# design.net
KiCad netlist of a schematic drawn in Altium Designer
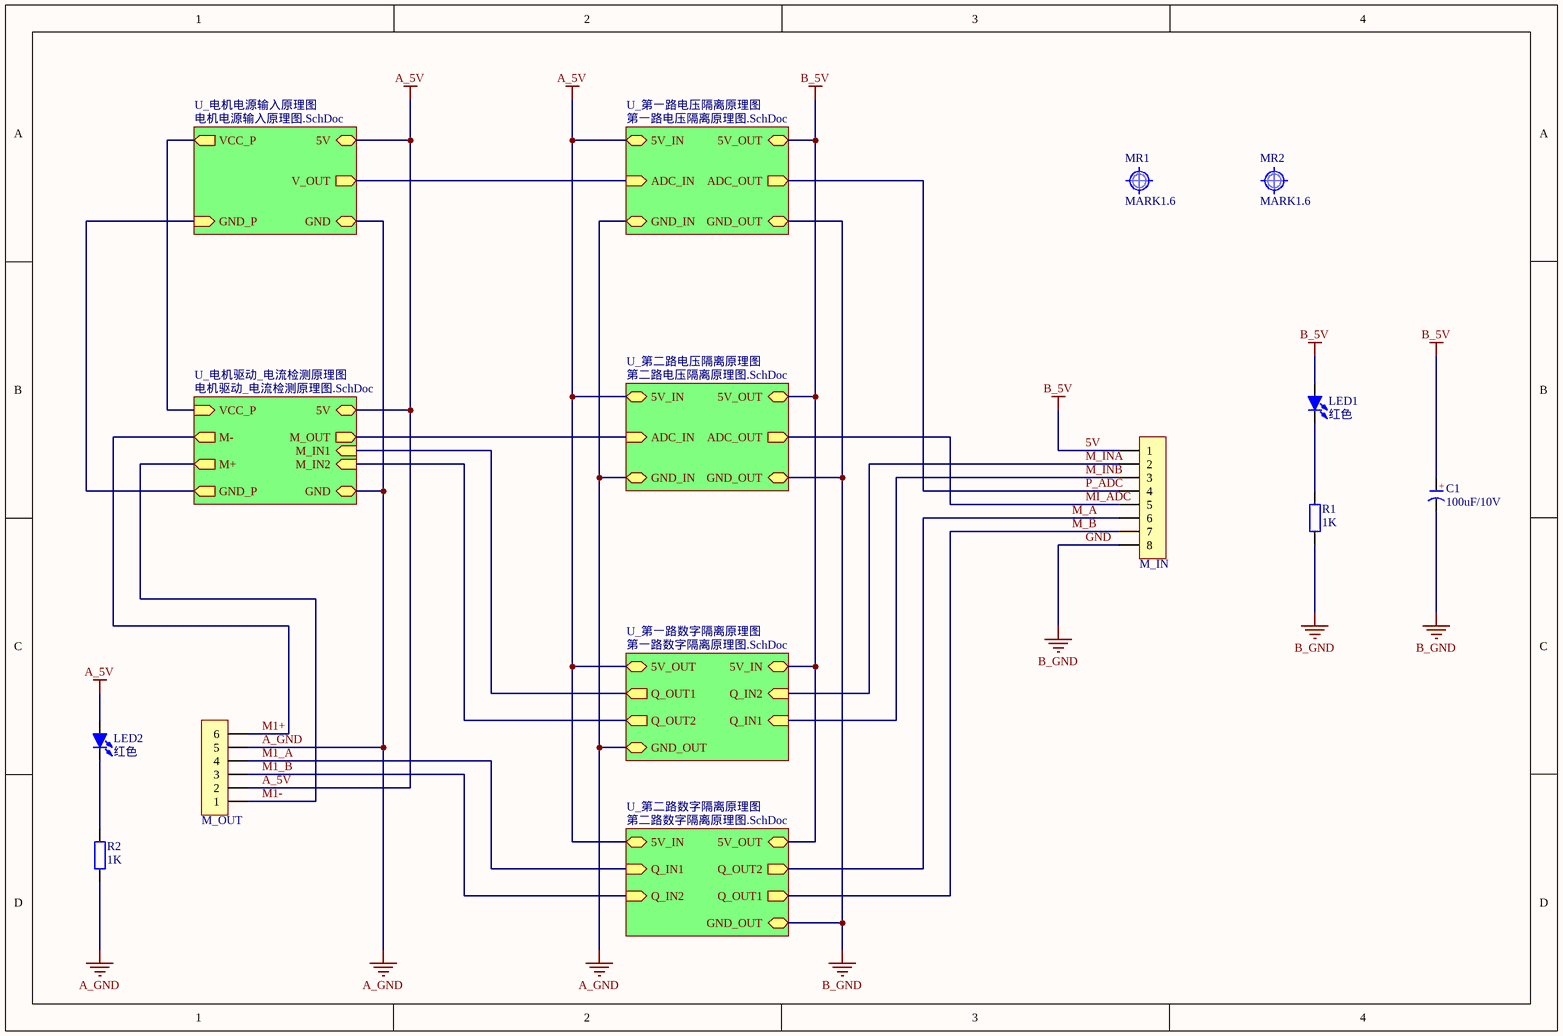
[diagram p0: 总原理框图.SchDoc]

(export (version "E")
  (design (tool "Eeschema 10.0.6"))
  (components
    (comp (ref "C1")
      (value "100uF/10V")
      (footprint "CD B(3528)")
      (description "贴片钽电容")
      (fields (field (name "版权归属") "源创客"))
      (libsource (lib "3.1   - 电阻-电容-电感") (part "C-CD"))
    )
    (comp (ref "LED1")
      (value "红色")
      (footprint "LED 0603W")
      (description "贴片LED")
      (fields (field (name "版权归属") "源创客"))
      (libsource (lib "9.1   - LED") (part "LED-SMD"))
    )
    (comp (ref "LED2")
      (value "红色")
      (footprint "LED 0603W")
      (description "贴片LED")
      (fields (field (name "版权归属") "源创客"))
      (libsource (lib "9.1   - LED") (part "LED-SMD"))
    )
    (comp (ref "MR1")
      (value "MARK1.6")
      (footprint "Mark 1.6")
      (description "光学定位点")
      (fields (field (name "版权归属") "源创客"))
      (libsource (lib "15.1 - 未分类器件") (part "MARK"))
    )
    (comp (ref "MR2")
      (value "MARK1.6")
      (footprint "Mark 1.6")
      (description "光学定位点")
      (fields (field (name "版权归属") "源创客"))
      (libsource (lib "15.1 - 未分类器件") (part "MARK"))
    )
    (comp (ref "M_IN")
      (value "HDR-1X8")
      (footprint "ZH1.5-WI-8P")
      (description "8P接插件")
      (fields (field (name "版权归属") "源创客"))
      (libsource (lib "4.4   - 接插件-脚距1.5") (part "Header 8"))
    )
    (comp (ref "M_OUT")
      (value "HDR-1X6")
      (footprint "PH2.0-WI-6P")
      (description "6P接插件")
      (fields (field (name "版权归属") "源创客"))
      (libsource (lib "4.5   - 接插件-脚距2.0") (part "Header 6"))
    )
    (comp (ref "R1")
      (value "1K")
      (footprint "R 0603_M")
      (description "贴片电阻")
      (fields (field (name "版权归属") "源创客"))
      (libsource (lib "3.1   - 电阻-电容-电感") (part "R"))
    )
    (comp (ref "R2")
      (value "1K")
      (footprint "R 0603_M")
      (description "贴片电阻")
      (fields (field (name "版权归属") "源创客"))
      (libsource (lib "3.1   - 电阻-电容-电感") (part "R"))
    )
  )
  (nets
    (net (code "2") (name "/M1+") (class "Default")
      (node (ref "M_OUT") (pin "6") (pinfunction "6_6") (pintype "passive"))
    )
    (net (code "3") (name "/M1-") (class "Default")
      (node (ref "M_OUT") (pin "1") (pinfunction "1_1") (pintype "passive"))
    )
    (net (code "4") (name "/M1_A") (class "Default")
      (node (ref "M_OUT") (pin "4") (pinfunction "4_4") (pintype "passive"))
    )
    (net (code "5") (name "/M1_B") (class "Default")
      (node (ref "M_OUT") (pin "3") (pinfunction "3_3") (pintype "passive"))
    )
    (net (code "6") (name "/MI_ADC") (class "Default")
      (node (ref "M_IN") (pin "5") (pinfunction "5_5") (pintype "passive"))
    )
    (net (code "7") (name "/M_A") (class "Default")
      (node (ref "M_IN") (pin "6") (pinfunction "6_6") (pintype "passive"))
    )
    (net (code "8") (name "/M_B") (class "Default")
      (node (ref "M_IN") (pin "7") (pinfunction "7_7") (pintype "passive"))
    )
    (net (code "9") (name "/M_INA") (class "Default")
      (node (ref "M_IN") (pin "2") (pinfunction "2_2") (pintype "passive"))
    )
    (net (code "10") (name "/M_INB") (class "Default")
      (node (ref "M_IN") (pin "3") (pinfunction "3_3") (pintype "passive"))
    )
    (net (code "12") (name "/P_ADC") (class "Default")
      (node (ref "M_IN") (pin "4") (pinfunction "4_4") (pintype "passive"))
    )
    (net (code "17") (name "A_5V") (class "Default")
      (node (ref "LED2") (pin "1") (pinfunction "A_1") (pintype "passive"))
      (node (ref "M_OUT") (pin "2") (pinfunction "2_2") (pintype "passive"))
    )
    (net (code "18") (name "A_GND") (class "Default")
      (node (ref "M_OUT") (pin "5") (pinfunction "5_5") (pintype "passive"))
      (node (ref "R2") (pin "1") (pinfunction "1_1") (pintype "passive"))
    )
    (net (code "19") (name "B_5V") (class "Default")
      (node (ref "C1") (pin "1") (pinfunction "A_1") (pintype "passive"))
      (node (ref "LED1") (pin "1") (pinfunction "A_1") (pintype "passive"))
      (node (ref "M_IN") (pin "1") (pinfunction "1_1") (pintype "passive"))
    )
    (net (code "20") (name "B_GND") (class "Default")
      (node (ref "C1") (pin "2") (pinfunction "K_2") (pintype "passive"))
      (node (ref "M_IN") (pin "8") (pinfunction "8_8") (pintype "passive"))
      (node (ref "R1") (pin "1") (pinfunction "1_1") (pintype "passive"))
    )
    (net (code "21") (name "Net-(LED1-K)") (class "Default")
      (node (ref "LED1") (pin "2") (pinfunction "K_2") (pintype "passive"))
      (node (ref "R1") (pin "2") (pinfunction "2_2") (pintype "passive"))
    )
    (net (code "22") (name "Net-(LED2-K)") (class "Default")
      (node (ref "LED2") (pin "2") (pinfunction "K_2") (pintype "passive"))
      (node (ref "R2") (pin "2") (pinfunction "2_2") (pintype "passive"))
    )
  )
)
